# Signal_imputs.net
KiCad netlist of a schematic drawn in Altium Designer
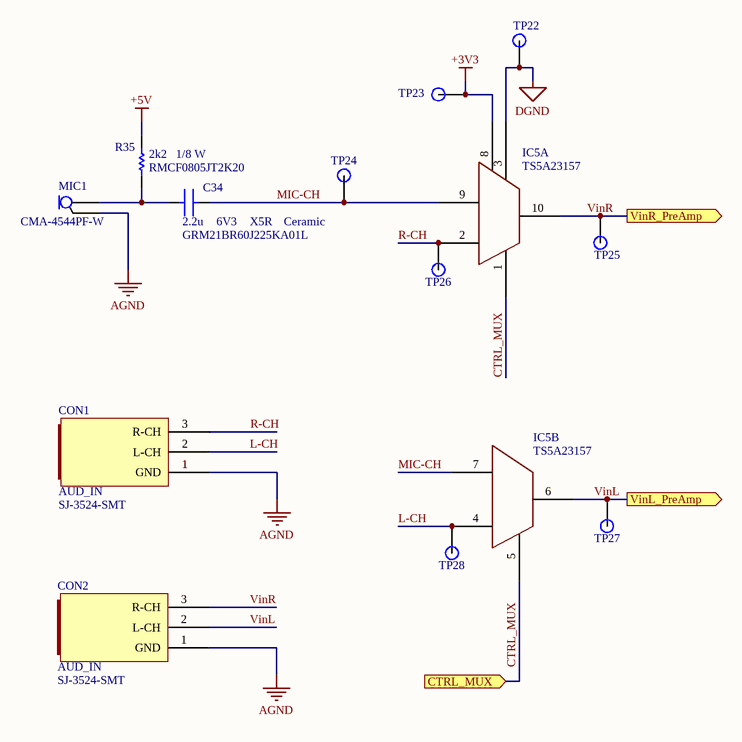
[diagram p0: Signal_imputs.SchDoc]

(export (version "E")
  (design (tool "Eeschema 10.0.6"))
  (components
    (comp (ref "C34")
      (value "2.2u 6V3 X5R Ceramic")
      (footprint "C_0805")
      (description "Capacitor")
      (fields
        (field (name "C") "2.2u")
        (field (name "V") "6V3")
        (field (name "TEMP COEF") "X5R")
        (field (name "PART NUMBER") "GRM21BR60J225KA01L")
        (field (name "MATERIAL") "Ceramic")
      )
      (libsource (lib "TDII_Lib_V2") (part "Cap1"))
    )
    (comp (ref "CON1")
      (value "AUD_IN")
      (footprint "AUDIO_JACK 3.5mm SMD")
      (fields (field (name "PART NUMBER") "SJ-3524-SMT"))
      (libsource (lib "TDII_Lib_V2") (part "Jack_1"))
    )
    (comp (ref "CON2")
      (value "AUD_IN")
      (footprint "AUDIO_JACK 3.5mm SMD")
      (fields (field (name "PART NUMBER") "SJ-3524-SMT"))
      (libsource (lib "TDII_Lib_V2") (part "Jack_1"))
    )
    (comp (ref "IC5")
      (value "TS5A23157")
      (footprint "TSSOP50P490X110-10N")
      (description "Analog Switch")
      (libsource (lib "TDII_Lib_V2") (part "A_SW_2x2{colon}1_VSSOP"))
    )
    (comp (ref "MIC1")
      (value "Mic")
      (footprint "MIC_CMA-4544PF-W")
      (description "Microfono")
      (fields (field (name "PART NUMBER") "CMA-4544PF-W"))
      (libsource (lib "TDII_Lib_V2") (part "Mic"))
    )
    (comp (ref "R35")
      (value "2k2")
      (footprint "R_0805")
      (description "Resistor")
      (fields
        (field (name "PART NUMBER") "RMCF0805JT2K20")
        (field (name "POWER") "1/8 W")
        (field (name "Comment") "2k2 1/8W")
      )
      (libsource (lib "TDII_Lib_V2") (part "Res1"))
    )
    (comp (ref "TP22")
      (value "TP")
      (footprint "TP")
      (description "Test Point")
      (libsource (lib "LituLib") (part "Test Point"))
    )
    (comp (ref "TP23")
      (value "TP")
      (footprint "TP")
      (description "Test Point")
      (libsource (lib "LituLib") (part "Test Point"))
    )
    (comp (ref "TP24")
      (value "TP")
      (footprint "TP")
      (description "Test Point")
      (libsource (lib "LituLib") (part "Test Point"))
    )
    (comp (ref "TP25")
      (value "TP")
      (footprint "TP")
      (description "Test Point")
      (libsource (lib "LituLib") (part "Test Point"))
    )
    (comp (ref "TP26")
      (value "TP")
      (footprint "TP")
      (description "Test Point")
      (libsource (lib "LituLib") (part "Test Point"))
    )
    (comp (ref "TP27")
      (value "TP")
      (footprint "TP")
      (description "Test Point")
      (libsource (lib "LituLib") (part "Test Point"))
    )
    (comp (ref "TP28")
      (value "TP")
      (footprint "TP")
      (description "Test Point")
      (libsource (lib "LituLib") (part "Test Point"))
    )
  )
  (nets
    (net (code "1") (name "+3V3") (class "Default")
      (node (ref "IC5") (pin "8") (pinfunction "VDD_8") (pintype "passive"))
      (node (ref "TP23") (pin "1") (pinfunction "1_1") (pintype "passive"))
    )
    (net (code "2") (name "+5V") (class "Default")
      (node (ref "R35") (pin "2") (pinfunction "2_2") (pintype "passive"))
    )
    (net (code "3") (name "/CTRL_MUX") (class "Default")
      (node (ref "IC5") (pin "1") (pinfunction "IN1_1") (pintype "passive"))
      (node (ref "IC5") (pin "5") (pinfunction "IN2_5") (pintype "passive"))
    )
    (net (code "4") (name "/L-CH") (class "Default")
      (node (ref "CON1") (pin "2") (pinfunction "L-CH_2") (pintype "passive"))
      (node (ref "IC5") (pin "4") (pinfunction "NO2_4") (pintype "passive"))
      (node (ref "TP28") (pin "1") (pinfunction "1_1") (pintype "passive"))
    )
    (net (code "5") (name "/MIC-CH") (class "Default")
      (node (ref "C34") (pin "2") (pinfunction "2_2") (pintype "passive"))
      (node (ref "IC5") (pin "7") (pinfunction "NC2_7") (pintype "passive"))
      (node (ref "IC5") (pin "9") (pinfunction "NC1_9") (pintype "passive"))
      (node (ref "TP24") (pin "1") (pinfunction "1_1") (pintype "passive"))
    )
    (net (code "6") (name "/R-CH") (class "Default")
      (node (ref "CON1") (pin "3") (pinfunction "R-CH_3") (pintype "passive"))
      (node (ref "IC5") (pin "2") (pinfunction "NO1_2") (pintype "passive"))
      (node (ref "TP26") (pin "1") (pinfunction "1_1") (pintype "passive"))
    )
    (net (code "7") (name "/VinL") (class "Default")
      (node (ref "CON2") (pin "2") (pinfunction "L-CH_2") (pintype "passive"))
      (node (ref "IC5") (pin "6") (pinfunction "COM2_6") (pintype "passive"))
      (node (ref "TP27") (pin "1") (pinfunction "1_1") (pintype "passive"))
    )
    (net (code "8") (name "/VinR") (class "Default")
      (node (ref "CON2") (pin "3") (pinfunction "R-CH_3") (pintype "passive"))
      (node (ref "IC5") (pin "10") (pinfunction "COM1_10") (pintype "passive"))
      (node (ref "TP25") (pin "1") (pinfunction "1_1") (pintype "passive"))
    )
    (net (code "9") (name "AGND") (class "Default")
      (node (ref "CON1") (pin "1") (pinfunction "GND_1") (pintype "passive"))
      (node (ref "CON2") (pin "1") (pinfunction "GND_1") (pintype "passive"))
      (node (ref "MIC1") (pin "2") (pinfunction "2_2") (pintype "passive"))
    )
    (net (code "10") (name "DGND") (class "Default")
      (node (ref "IC5") (pin "3") (pinfunction "DGND_3") (pintype "passive"))
      (node (ref "TP22") (pin "1") (pinfunction "1_1") (pintype "passive"))
    )
    (net (code "11") (name "Net-(C34-Pad1)") (class "Default")
      (node (ref "C34") (pin "1") (pinfunction "1_1") (pintype "passive"))
      (node (ref "MIC1") (pin "1") (pinfunction "1_1") (pintype "passive"))
      (node (ref "R35") (pin "1") (pinfunction "1_1") (pintype "passive"))
    )
  )
)
